# Snickerdoodle_PS.net
KiCad netlist of a schematic drawn in Altium Designer
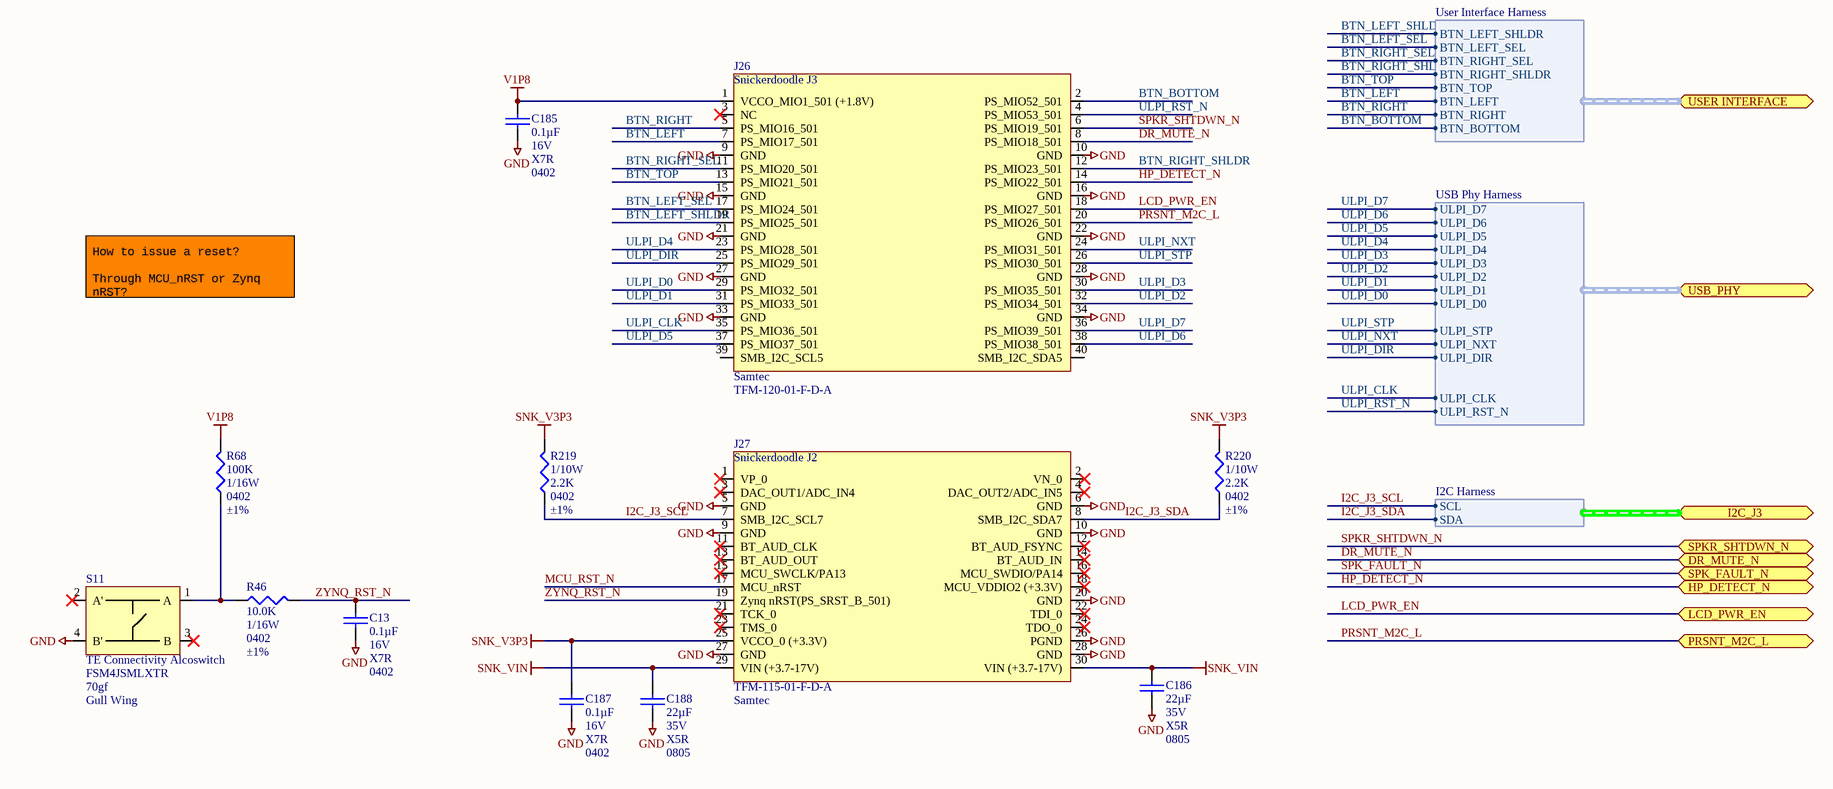
[diagram p0: Snickerdoodle PS.SchDoc]

(export (version "E")
  (design (tool "Eeschema 10.0.6"))
  (components
    (comp (ref "C13")
      (value "0.1uF")
      (footprint "C_0402")
      (description "CAP CER .10UF 16V X7R 0402")
      (fields
        (field (name "MANUFACTURER") "Murata Electronics North America")
        (field (name "MANUFACTURER PART NUMBER") "GRM155R71C104KA88J")
        (field (name "CAPACITANCE") "0.1µF")
        (field (name "VOLTAGE - RATED") "16V")
        (field (name "TEMPERATURE COEFFICIENT") "X7R")
        (field (name "PACKAGE / CASE") "0402")
      )
      (libsource (lib "Main LibraryX") (part "C_0402_0.1UF_16V"))
    )
    (comp (ref "C185")
      (value "0.1uF")
      (footprint "C_0402")
      (description "CAP CER .10UF 16V X7R 0402")
      (fields
        (field (name "MANUFACTURER") "Murata Electronics North America")
        (field (name "MANUFACTURER PART NUMBER") "GRM155R71C104KA88J")
        (field (name "CAPACITANCE") "0.1µF")
        (field (name "VOLTAGE - RATED") "16V")
        (field (name "TEMPERATURE COEFFICIENT") "X7R")
        (field (name "PACKAGE / CASE") "0402")
      )
      (libsource (lib "Main LibraryX") (part "C_0402_0.1UF_16V"))
    )
    (comp (ref "C186")
      (value "C_0805_22µF_35V")
      (footprint "C_ERA-0805")
      (description "CAP CER 22UF 35V X5R 0805")
      (fields
        (field (name "MANUFACTURER") "TDK Corporation")
        (field (name "MANUFACTURER PART NUMBER") "C2012X5R1V226M125AC")
        (field (name "CAPACITANCE") "22µF")
        (field (name "VOLTAGE - RATED") "35V")
        (field (name "TEMPERATURE COEFFICIENT") "X5R")
        (field (name "PACKAGE / CASE") "0805")
      )
      (libsource (lib "Cospan Design") (part "C_0805_22µF_35V"))
    )
    (comp (ref "C187")
      (value "0.1uF")
      (footprint "C_0402")
      (description "CAP CER .10UF 16V X7R 0402")
      (fields
        (field (name "MANUFACTURER") "Murata Electronics North America")
        (field (name "MANUFACTURER PART NUMBER") "GRM155R71C104KA88J")
        (field (name "CAPACITANCE") "0.1µF")
        (field (name "VOLTAGE - RATED") "16V")
        (field (name "TEMPERATURE COEFFICIENT") "X7R")
        (field (name "PACKAGE / CASE") "0402")
      )
      (libsource (lib "Main LibraryX") (part "C_0402_0.1UF_16V"))
    )
    (comp (ref "C188")
      (value "C_0805_22µF_35V")
      (footprint "C_ERA-0805")
      (description "CAP CER 22UF 35V X5R 0805")
      (fields
        (field (name "MANUFACTURER") "TDK Corporation")
        (field (name "MANUFACTURER PART NUMBER") "C2012X5R1V226M125AC")
        (field (name "CAPACITANCE") "22µF")
        (field (name "VOLTAGE - RATED") "35V")
        (field (name "TEMPERATURE COEFFICIENT") "X5R")
        (field (name "PACKAGE / CASE") "0805")
      )
      (libsource (lib "Cospan Design") (part "C_0805_22µF_35V"))
    )
    (comp (ref "J26")
      (value "J_SNICKERDOODLE_J3")
      (footprint "TFM12001-X-D-A")
      (description "SNICKERDOODLE J3")
      (fields
        (field (name "MANUFACTURER") "Samtec")
        (field (name "MANUFACTURER PART NUMBER") "TFM-120-01-F-D-A")
      )
      (libsource (lib "Cospan Design") (part "J_SNICKERDOODLE_J3"))
    )
    (comp (ref "J27")
      (value "J_SNICKERDOODLE_J2")
      (footprint "TFM11501-X-D-A")
      (description "SNICKERDOODLE J2")
      (fields
        (field (name "MANUFACTURER PART NUMBER") "TFM-115-01-F-D-A")
        (field (name "MANUFACTURER") "Samtec")
      )
      (libsource (lib "Cospan Design") (part "J_SNICKERDOODLE_J2"))
    )
    (comp (ref "R46")
      (value "R_0402_10.0K")
      (footprint "R_0402")
      (description "RES 10.0K OHM 1/16W 1% 0402 SMD")
      (fields
        (field (name "MANUFACTURER") "Stackpole Electronics Inc")
        (field (name "MANUFACTURER PART NUMBER") "RMCF0402FT10K0")
        (field (name "RESISTANCE IN OHMS") "10.0K")
        (field (name "POWER (WATTS)") "1/16W")
        (field (name "CASE") "0402")
        (field (name "TOLERANCE") "±1%")
      )
      (libsource (lib "Cospan Design") (part "R_0402_10.0K"))
    )
    (comp (ref "R68")
      (value "R_0402_100K")
      (footprint "R_0402")
      (description "RES SMD 100K OHM 1% 1/16W 0402")
      (fields
        (field (name "MANUFACTURER") "Yageo")
        (field (name "MANUFACTURER PART NUMBER") "RC0402FR-07100KL")
        (field (name "RESISTANCE IN OHMS") "100K")
        (field (name "POWER (WATTS)") "1/16W")
        (field (name "CASE") "0402")
        (field (name "TOLERANCE") "±1%")
      )
      (libsource (lib "Cospan Design") (part "R_0402_100K"))
    )
    (comp (ref "R219")
      (value "2.2k Ohms")
      (footprint "R_0402")
      (description "RES 2.20K OHM 1/10W 1% 0402 SMD")
      (fields
        (field (name "MANUFACTURER") "Yageo")
        (field (name "MANUFACTURER PART NUMBER") "RC0402FR-072K2L")
        (field (name "POWER (WATTS)") "1/10W")
        (field (name "RESISTANCE IN OHMS") "2.2K")
        (field (name "CASE") "0402")
        (field (name "TOLERANCE") "±1%")
      )
      (libsource (lib "Main Library") (part "R_0402_2.2K"))
    )
    (comp (ref "R220")
      (value "2.2k Ohms")
      (footprint "R_0402")
      (description "RES 2.20K OHM 1/10W 1% 0402 SMD")
      (fields
        (field (name "MANUFACTURER") "Yageo")
        (field (name "MANUFACTURER PART NUMBER") "RC0402FR-072K2L")
        (field (name "POWER (WATTS)") "1/10W")
        (field (name "RESISTANCE IN OHMS") "2.2K")
        (field (name "CASE") "0402")
        (field (name "TOLERANCE") "±1%")
      )
      (libsource (lib "Main Library") (part "R_0402_2.2K"))
    )
    (comp (ref "S11")
      (value "S_TACTILE_1571563_2_BUTTON")
      (footprint "TACTILE_1571563_2")
      (description "SWITCH TACTILE SPST-NO 0.05A 24V")
      (fields
        (field (name "MANUFACTURER") "TE Connectivity Alcoswitch")
        (field (name "MANUFACTURER PART NUMBER") "FSM4JSMLXTR")
        (field (name "OPERATING FORCE") "70gf")
        (field (name "TERMINATION") "Gull Wing")
      )
      (libsource (lib "Cospan Design") (part "S_TACTILE_1571563_2_BUTTON"))
    )
  )
  (nets
    (net (code "7") (name "/BTN_BOTTOM") (class "Default")
      (node (ref "J26") (pin "2") (pinfunction "PS_MIO52_501_2") (pintype "passive"))
    )
    (net (code "8") (name "/BTN_LEFT") (class "Default")
      (node (ref "J26") (pin "7") (pinfunction "PS_MIO17_501_7") (pintype "passive"))
    )
    (net (code "9") (name "/BTN_LEFT_SEL") (class "Default")
      (node (ref "J26") (pin "17") (pinfunction "PS_MIO24_501_17") (pintype "passive"))
    )
    (net (code "10") (name "/BTN_LEFT_SHLDR") (class "Default")
      (node (ref "J26") (pin "19") (pinfunction "PS_MIO25_501_19") (pintype "passive"))
    )
    (net (code "11") (name "/BTN_RIGHT") (class "Default")
      (node (ref "J26") (pin "5") (pinfunction "PS_MIO16_501_5") (pintype "passive"))
    )
    (net (code "12") (name "/BTN_RIGHT_SEL") (class "Default")
      (node (ref "J26") (pin "11") (pinfunction "PS_MIO20_501_11") (pintype "passive"))
    )
    (net (code "13") (name "/BTN_RIGHT_SHLDR") (class "Default")
      (node (ref "J26") (pin "12") (pinfunction "PS_MIO23_501_12") (pintype "passive"))
    )
    (net (code "14") (name "/BTN_TOP") (class "Default")
      (node (ref "J26") (pin "13") (pinfunction "PS_MIO21_501_13") (pintype "passive"))
    )
    (net (code "15") (name "/DR_MUTE_N") (class "Default")
      (node (ref "J26") (pin "8") (pinfunction "PS_MIO18_501_8") (pintype "passive"))
    )
    (net (code "16") (name "/HP_DETECT_N") (class "Default")
      (node (ref "J26") (pin "14") (pinfunction "PS_MIO22_501_14") (pintype "passive"))
    )
    (net (code "17") (name "/I2C_J3_SCL") (class "Default")
      (node (ref "J27") (pin "7") (pinfunction "SMB_I2C_SCL7_7") (pintype "passive"))
      (node (ref "R219") (pin "2") (pinfunction "2_2") (pintype "passive"))
    )
    (net (code "18") (name "/I2C_J3_SDA") (class "Default")
      (node (ref "J27") (pin "8") (pinfunction "SMB_I2C_SDA7_8") (pintype "passive"))
      (node (ref "R220") (pin "2") (pinfunction "2_2") (pintype "passive"))
    )
    (net (code "19") (name "/LCD_PWR_EN") (class "Default")
      (node (ref "J26") (pin "18") (pinfunction "PS_MIO27_501_18") (pintype "passive"))
    )
    (net (code "20") (name "/MCU_RST_N") (class "Default")
      (node (ref "J27") (pin "17") (pinfunction "MCU_nRST_17") (pintype "passive"))
    )
    (net (code "21") (name "/PRSNT_M2C_L") (class "Default")
      (node (ref "J26") (pin "20") (pinfunction "PS_MIO26_501_20") (pintype "passive"))
    )
    (net (code "22") (name "/SPKR_SHTDWN_N") (class "Default")
      (node (ref "J26") (pin "6") (pinfunction "PS_MIO19_501_6") (pintype "passive"))
    )
    (net (code "24") (name "/ULPI_CLK") (class "Default")
      (node (ref "J26") (pin "35") (pinfunction "PS_MIO36_501_35") (pintype "passive"))
    )
    (net (code "25") (name "/ULPI_D0") (class "Default")
      (node (ref "J26") (pin "29") (pinfunction "PS_MIO32_501_29") (pintype "passive"))
    )
    (net (code "26") (name "/ULPI_D1") (class "Default")
      (node (ref "J26") (pin "31") (pinfunction "PS_MIO33_501_31") (pintype "passive"))
    )
    (net (code "27") (name "/ULPI_D2") (class "Default")
      (node (ref "J26") (pin "32") (pinfunction "PS_MIO34_501_32") (pintype "passive"))
    )
    (net (code "28") (name "/ULPI_D3") (class "Default")
      (node (ref "J26") (pin "30") (pinfunction "PS_MIO35_501_30") (pintype "passive"))
    )
    (net (code "29") (name "/ULPI_D4") (class "Default")
      (node (ref "J26") (pin "23") (pinfunction "PS_MIO28_501_23") (pintype "passive"))
    )
    (net (code "30") (name "/ULPI_D5") (class "Default")
      (node (ref "J26") (pin "37") (pinfunction "PS_MIO37_501_37") (pintype "passive"))
    )
    (net (code "31") (name "/ULPI_D6") (class "Default")
      (node (ref "J26") (pin "38") (pinfunction "PS_MIO38_501_38") (pintype "passive"))
    )
    (net (code "32") (name "/ULPI_D7") (class "Default")
      (node (ref "J26") (pin "36") (pinfunction "PS_MIO39_501_36") (pintype "passive"))
    )
    (net (code "33") (name "/ULPI_DIR") (class "Default")
      (node (ref "J26") (pin "25") (pinfunction "PS_MIO29_501_25") (pintype "passive"))
    )
    (net (code "34") (name "/ULPI_NXT") (class "Default")
      (node (ref "J26") (pin "24") (pinfunction "PS_MIO31_501_24") (pintype "passive"))
    )
    (net (code "35") (name "/ULPI_RST_N") (class "Default")
      (node (ref "J26") (pin "4") (pinfunction "PS_MIO53_501_4") (pintype "passive"))
    )
    (net (code "36") (name "/ULPI_STP") (class "Default")
      (node (ref "J26") (pin "26") (pinfunction "PS_MIO30_501_26") (pintype "passive"))
    )
    (net (code "37") (name "/ZYNQ_RST_N") (class "Default")
      (node (ref "C13") (pin "2") (pinfunction "2_2") (pintype "passive"))
      (node (ref "J27") (pin "19") (pinfunction "Zynq_nRST(PS_SRST_B_501)_19") (pintype "passive"))
      (node (ref "R46") (pin "1") (pinfunction "1_1") (pintype "passive"))
    )
    (net (code "41") (name "GND") (class "Default")
      (node (ref "C13") (pin "1") (pinfunction "1_1") (pintype "passive"))
      (node (ref "C185") (pin "1") (pinfunction "1_1") (pintype "passive"))
      (node (ref "C186") (pin "1") (pinfunction "1_1") (pintype "passive"))
      (node (ref "C187") (pin "1") (pinfunction "1_1") (pintype "passive"))
      (node (ref "C188") (pin "1") (pinfunction "1_1") (pintype "passive"))
      (node (ref "J26") (pin "10") (pinfunction "GND_10") (pintype "passive"))
      (node (ref "J26") (pin "15") (pinfunction "GND_15") (pintype "passive"))
      (node (ref "J26") (pin "16") (pinfunction "GND_16") (pintype "passive"))
      (node (ref "J26") (pin "21") (pinfunction "GND_21") (pintype "passive"))
      (node (ref "J26") (pin "22") (pinfunction "GND_22") (pintype "passive"))
      (node (ref "J26") (pin "27") (pinfunction "GND_27") (pintype "passive"))
      (node (ref "J26") (pin "28") (pinfunction "GND_28") (pintype "passive"))
      (node (ref "J26") (pin "33") (pinfunction "GND_33") (pintype "passive"))
      (node (ref "J26") (pin "34") (pinfunction "GND_34") (pintype "passive"))
      (node (ref "J26") (pin "9") (pinfunction "GND_9") (pintype "passive"))
      (node (ref "J27") (pin "10") (pinfunction "GND_10") (pintype "passive"))
      (node (ref "J27") (pin "20") (pinfunction "GND_20") (pintype "passive"))
      (node (ref "J27") (pin "26") (pinfunction "PGND_26") (pintype "passive"))
      (node (ref "J27") (pin "27") (pinfunction "GND_27") (pintype "passive"))
      (node (ref "J27") (pin "28") (pinfunction "GND_28") (pintype "passive"))
      (node (ref "J27") (pin "5") (pinfunction "GND_5") (pintype "passive"))
      (node (ref "J27") (pin "6") (pinfunction "GND_6") (pintype "passive"))
      (node (ref "J27") (pin "9") (pinfunction "GND_9") (pintype "passive"))
      (node (ref "S11") (pin "4") (pinfunction "B'_4") (pintype "passive"))
    )
    (net (code "42") (name "Net-(S11-A)") (class "Default")
      (node (ref "R46") (pin "2") (pinfunction "2_2") (pintype "passive"))
      (node (ref "R68") (pin "2") (pinfunction "2_2") (pintype "passive"))
      (node (ref "S11") (pin "1") (pinfunction "A_1") (pintype "passive"))
    )
    (net (code "43") (name "SNK_V3P3") (class "Default")
      (node (ref "C187") (pin "2") (pinfunction "2_2") (pintype "passive"))
      (node (ref "J27") (pin "25") (pinfunction "VCCO_0_(+3.3V)_25") (pintype "passive"))
      (node (ref "R219") (pin "1") (pinfunction "1_1") (pintype "passive"))
      (node (ref "R220") (pin "1") (pinfunction "1_1") (pintype "passive"))
    )
    (net (code "44") (name "SNK_VIN") (class "Default")
      (node (ref "C186") (pin "2") (pinfunction "2_2") (pintype "passive"))
      (node (ref "C188") (pin "2") (pinfunction "2_2") (pintype "passive"))
      (node (ref "J27") (pin "29") (pinfunction "VIN_(+3.7-17V)_29") (pintype "passive"))
      (node (ref "J27") (pin "30") (pinfunction "VIN_(+3.7-17V)_30") (pintype "passive"))
    )
    (net (code "45") (name "V1P8") (class "Default")
      (node (ref "C185") (pin "2") (pinfunction "2_2") (pintype "passive"))
      (node (ref "J26") (pin "1") (pinfunction "VCCO_MIO1_501_(+1.8V)_1") (pintype "passive"))
      (node (ref "R68") (pin "1") (pinfunction "1_1") (pintype "passive"))
    )
    (net (code "46") (name "unconnected-(J26-NC-Pad3)") (class "Default")
      (node (ref "J26") (pin "3") (pinfunction "NC_3") (pintype "passive+no_connect"))
    )
    (net (code "47") (name "unconnected-(J26-SMB_I2C_SCL5-Pad39)") (class "Default")
      (node (ref "J26") (pin "39") (pinfunction "SMB_I2C_SCL5_39") (pintype "passive"))
    )
    (net (code "48") (name "unconnected-(J26-SMB_I2C_SDA5-Pad40)") (class "Default")
      (node (ref "J26") (pin "40") (pinfunction "SMB_I2C_SDA5_40") (pintype "passive"))
    )
    (net (code "49") (name "unconnected-(J27-BT_AUD_CLK-Pad11)") (class "Default")
      (node (ref "J27") (pin "11") (pinfunction "BT_AUD_CLK_11") (pintype "passive+no_connect"))
    )
    (net (code "50") (name "unconnected-(J27-BT_AUD_FSYNC-Pad12)") (class "Default")
      (node (ref "J27") (pin "12") (pinfunction "BT_AUD_FSYNC_12") (pintype "passive+no_connect"))
    )
    (net (code "51") (name "unconnected-(J27-BT_AUD_IN-Pad14)") (class "Default")
      (node (ref "J27") (pin "14") (pinfunction "BT_AUD_IN_14") (pintype "passive+no_connect"))
    )
    (net (code "52") (name "unconnected-(J27-BT_AUD_OUT-Pad13)") (class "Default")
      (node (ref "J27") (pin "13") (pinfunction "BT_AUD_OUT_13") (pintype "passive+no_connect"))
    )
    (net (code "53") (name "unconnected-(J27-DAC_OUT1{slash}ADC_IN4-Pad3)") (class "Default")
      (node (ref "J27") (pin "3") (pinfunction "DAC_OUT1/ADC_IN4_3") (pintype "passive+no_connect"))
    )
    (net (code "54") (name "unconnected-(J27-DAC_OUT2{slash}ADC_IN5-Pad4)") (class "Default")
      (node (ref "J27") (pin "4") (pinfunction "DAC_OUT2/ADC_IN5_4") (pintype "passive+no_connect"))
    )
    (net (code "55") (name "unconnected-(J27-MCU_SWCLK{slash}PA13-Pad15)") (class "Default")
      (node (ref "J27") (pin "15") (pinfunction "MCU_SWCLK/PA13_15") (pintype "passive+no_connect"))
    )
    (net (code "56") (name "unconnected-(J27-MCU_SWDIO{slash}PA14-Pad16)") (class "Default")
      (node (ref "J27") (pin "16") (pinfunction "MCU_SWDIO/PA14_16") (pintype "passive+no_connect"))
    )
    (net (code "57") (name "unconnected-(J27-MCU_VDDIO2_(+3.3V)-Pad18)") (class "Default")
      (node (ref "J27") (pin "18") (pinfunction "MCU_VDDIO2_(+3.3V)_18") (pintype "passive+no_connect"))
    )
    (net (code "58") (name "unconnected-(J27-TCK_0-Pad21)") (class "Default")
      (node (ref "J27") (pin "21") (pinfunction "TCK_0_21") (pintype "passive+no_connect"))
    )
    (net (code "59") (name "unconnected-(J27-TDI_0-Pad22)") (class "Default")
      (node (ref "J27") (pin "22") (pinfunction "TDI_0_22") (pintype "passive+no_connect"))
    )
    (net (code "60") (name "unconnected-(J27-TDO_0-Pad24)") (class "Default")
      (node (ref "J27") (pin "24") (pinfunction "TDO_0_24") (pintype "passive+no_connect"))
    )
    (net (code "61") (name "unconnected-(J27-TMS_0-Pad23)") (class "Default")
      (node (ref "J27") (pin "23") (pinfunction "TMS_0_23") (pintype "passive+no_connect"))
    )
    (net (code "62") (name "unconnected-(J27-VN_0-Pad2)") (class "Default")
      (node (ref "J27") (pin "2") (pinfunction "VN_0_2") (pintype "passive+no_connect"))
    )
    (net (code "63") (name "unconnected-(J27-VP_0-Pad1)") (class "Default")
      (node (ref "J27") (pin "1") (pinfunction "VP_0_1") (pintype "passive+no_connect"))
    )
    (net (code "64") (name "unconnected-(S11-A'-Pad2)") (class "Default")
      (node (ref "S11") (pin "2") (pinfunction "A'_2") (pintype "passive+no_connect"))
    )
    (net (code "65") (name "unconnected-(S11-B-Pad3)") (class "Default")
      (node (ref "S11") (pin "3") (pinfunction "B_3") (pintype "passive+no_connect"))
    )
  )
)
